# Decoder.net
KiCad netlist of a schematic drawn in Altium Designer
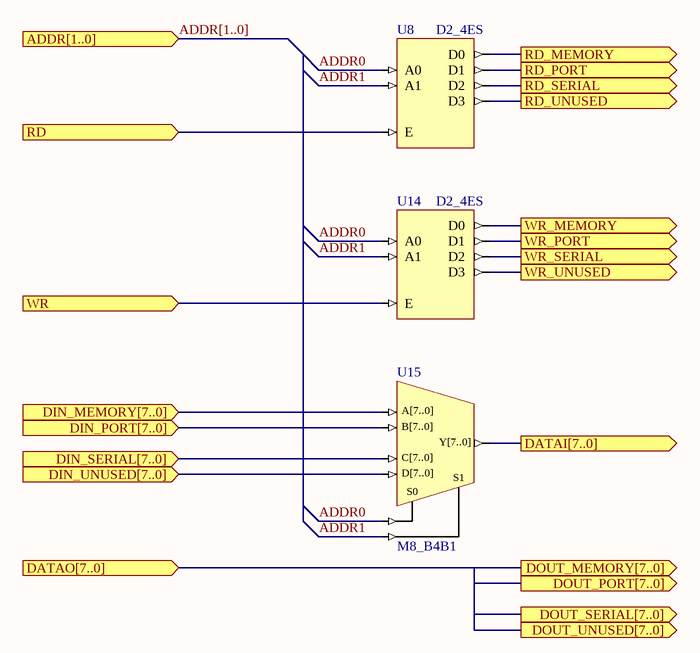
[diagram p0: Decoder.SCHDOC]

(export (version "E")
  (design (tool "Eeschema 10.0.6"))
  (components
    (comp (ref "U8")
      (value "D2_4ES")
      (description "Binary 2- to 4-Bit Decoder with Enable, Single Pin Version")
      (fields (field (name "PUBLISHER") "Altium Limited"))
      (libsource (lib "FPGA Generic") (part "D2_4ES"))
    )
    (comp (ref "U14")
      (value "D2_4ES")
      (description "Binary 2- to 4-Bit Decoder with Enable, Single Pin Version")
      (fields (field (name "PUBLISHER") "Altium Limited"))
      (libsource (lib "FPGA Generic") (part "D2_4ES"))
    )
    (comp (ref "U15")
      (value "M8_B4B1")
      (description "4x8-Bit Bus to 1x8-Bit Bus Multiplexer")
      (fields (field (name "PUBLISHER") "Altium Limited"))
      (libsource (lib "FPGA Generic") (part "M8_B4B1"))
    )
  )
  (nets
    (net (code "73") (name "/ADDR0") (class "Default")
      (node (ref "U14") (pin "A0") (pinfunction "A0_A0") (pintype "input"))
      (node (ref "U15") (pin "S0") (pinfunction "S0_S0") (pintype "input"))
      (node (ref "U8") (pin "A0") (pinfunction "A0_A0") (pintype "input"))
    )
    (net (code "74") (name "/ADDR1") (class "Default")
      (node (ref "U14") (pin "A1") (pinfunction "A1_A1") (pintype "input"))
      (node (ref "U15") (pin "S1") (pinfunction "S1_S1") (pintype "input"))
      (node (ref "U8") (pin "A1") (pinfunction "A1_A1") (pintype "input"))
    )
    (net (code "76") (name "/DATAI[7..0]") (class "Default")
      (node (ref "U15") (pin "Y[7..0]") (pinfunction "Y[7..0]_Y[7..0]") (pintype "output"))
    )
    (net (code "78") (name "/DIN_MEMORY[7..0]") (class "Default")
      (node (ref "U15") (pin "A[7..0]") (pinfunction "A[7..0]_A[7..0]") (pintype "input"))
    )
    (net (code "79") (name "/DIN_PORT[7..0]") (class "Default")
      (node (ref "U15") (pin "B[7..0]") (pinfunction "B[7..0]_B[7..0]") (pintype "input"))
    )
    (net (code "80") (name "/DIN_SERIAL[7..0]") (class "Default")
      (node (ref "U15") (pin "C[7..0]") (pinfunction "C[7..0]_C[7..0]") (pintype "input"))
    )
    (net (code "81") (name "/DIN_UNUSED[7..0]") (class "Default")
      (node (ref "U15") (pin "D[7..0]") (pinfunction "D[7..0]_D[7..0]") (pintype "input"))
    )
    (net (code "85") (name "/RD") (class "Default")
      (node (ref "U8") (pin "E") (pinfunction "E_E") (pintype "input"))
    )
    (net (code "86") (name "/RD_MEMORY") (class "Default")
      (node (ref "U8") (pin "D0") (pinfunction "D0_D0") (pintype "output"))
    )
    (net (code "87") (name "/RD_PORT") (class "Default")
      (node (ref "U8") (pin "D1") (pinfunction "D1_D1") (pintype "output"))
    )
    (net (code "88") (name "/RD_SERIAL") (class "Default")
      (node (ref "U8") (pin "D2") (pinfunction "D2_D2") (pintype "output"))
    )
    (net (code "89") (name "/RD_UNUSED") (class "Default")
      (node (ref "U8") (pin "D3") (pinfunction "D3_D3") (pintype "output"))
    )
    (net (code "90") (name "/WR") (class "Default")
      (node (ref "U14") (pin "E") (pinfunction "E_E") (pintype "input"))
    )
    (net (code "91") (name "/WR_MEMORY") (class "Default")
      (node (ref "U14") (pin "D0") (pinfunction "D0_D0") (pintype "output"))
    )
    (net (code "92") (name "/WR_PORT") (class "Default")
      (node (ref "U14") (pin "D1") (pinfunction "D1_D1") (pintype "output"))
    )
    (net (code "93") (name "/WR_SERIAL") (class "Default")
      (node (ref "U14") (pin "D2") (pinfunction "D2_D2") (pintype "output"))
    )
    (net (code "94") (name "/WR_UNUSED") (class "Default")
      (node (ref "U14") (pin "D3") (pinfunction "D3_D3") (pintype "output"))
    )
  )
)
